# buttons.net
KiCad netlist of a schematic drawn in EAGLE
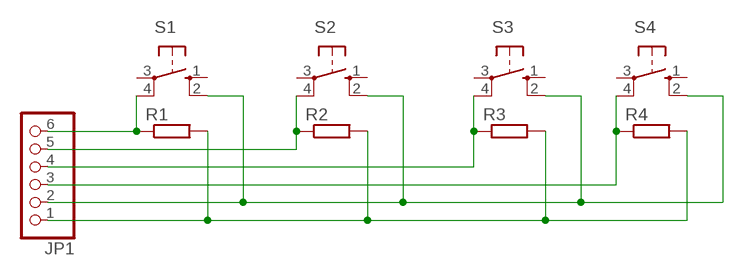
[diagram p0: schematic, sheet 1]

(export (version "E")
  (design (tool "Eeschema 10.0.6"))
  (components
    (comp (ref "JP1")
      (value "PINHD-1X6/90")
      (footprint "eagle-import:1X06_90")
      (libsource (lib "eagle-import") (part "PINHD-1X6/90"))
    )
    (comp (ref "R1")
      (value "R-EU_0207/10")
      (footprint "eagle-import:0207_10")
      (libsource (lib "eagle-import") (part "R-EU_0207/10"))
    )
    (comp (ref "R2")
      (value "R-EU_0207/10")
      (footprint "eagle-import:0207_10")
      (libsource (lib "eagle-import") (part "R-EU_0207/10"))
    )
    (comp (ref "R3")
      (value "R-EU_0207/10")
      (footprint "eagle-import:0207_10")
      (libsource (lib "eagle-import") (part "R-EU_0207/10"))
    )
    (comp (ref "R4")
      (value "R-EU_0207/10")
      (footprint "eagle-import:0207_10")
      (libsource (lib "eagle-import") (part "R-EU_0207/10"))
    )
    (comp (ref "S1")
      (value "10-XX")
      (footprint "eagle-import:B3F-10XX")
      (fields (field (name "MPN") "B3F-1000"))
      (libsource (lib "eagle-import") (part "10-XX"))
    )
    (comp (ref "S2")
      (value "10-XX")
      (footprint "eagle-import:B3F-10XX")
      (fields (field (name "MPN") "B3F-1000"))
      (libsource (lib "eagle-import") (part "10-XX"))
    )
    (comp (ref "S3")
      (value "10-XX")
      (footprint "eagle-import:B3F-10XX")
      (fields (field (name "MPN") "B3F-1000"))
      (libsource (lib "eagle-import") (part "10-XX"))
    )
    (comp (ref "S4")
      (value "10-XX")
      (footprint "eagle-import:B3F-10XX")
      (fields (field (name "MPN") "B3F-1000"))
      (libsource (lib "eagle-import") (part "10-XX"))
    )
  )
  (nets
    (net (code "1") (name "Net-(JP1-Pad1)") (class "Default")
      (node (ref "JP1") (pin "1") (pinfunction "1_1") (pintype "passive"))
      (node (ref "R1") (pin "2") (pinfunction "2_2") (pintype "passive"))
      (node (ref "R2") (pin "2") (pinfunction "2_2") (pintype "passive"))
      (node (ref "R3") (pin "2") (pinfunction "2_2") (pintype "passive"))
      (node (ref "R4") (pin "2") (pinfunction "2_2") (pintype "passive"))
    )
    (net (code "2") (name "Net-(S1-P1)") (class "Default")
      (node (ref "JP1") (pin "6") (pinfunction "6_6") (pintype "passive"))
      (node (ref "R1") (pin "1") (pinfunction "1_1") (pintype "passive"))
      (node (ref "S1") (pin "4") (pinfunction "P1_4") (pintype "passive"))
    )
    (net (code "3") (name "Net-(S1-S1)") (class "Default")
      (node (ref "JP1") (pin "2") (pinfunction "2_2") (pintype "passive"))
      (node (ref "S1") (pin "2") (pinfunction "S1_2") (pintype "passive"))
      (node (ref "S2") (pin "2") (pinfunction "S1_2") (pintype "passive"))
      (node (ref "S3") (pin "2") (pinfunction "S1_2") (pintype "passive"))
      (node (ref "S4") (pin "2") (pinfunction "S1_2") (pintype "passive"))
    )
    (net (code "4") (name "Net-(S2-P1)") (class "Default")
      (node (ref "JP1") (pin "5") (pinfunction "5_5") (pintype "passive"))
      (node (ref "R2") (pin "1") (pinfunction "1_1") (pintype "passive"))
      (node (ref "S2") (pin "4") (pinfunction "P1_4") (pintype "passive"))
    )
    (net (code "5") (name "Net-(S3-P1)") (class "Default")
      (node (ref "JP1") (pin "4") (pinfunction "4_4") (pintype "passive"))
      (node (ref "R3") (pin "1") (pinfunction "1_1") (pintype "passive"))
      (node (ref "S3") (pin "4") (pinfunction "P1_4") (pintype "passive"))
    )
    (net (code "6") (name "Net-(S4-P1)") (class "Default")
      (node (ref "JP1") (pin "3") (pinfunction "3_3") (pintype "passive"))
      (node (ref "R4") (pin "1") (pinfunction "1_1") (pintype "passive"))
      (node (ref "S4") (pin "4") (pinfunction "P1_4") (pintype "passive"))
    )
    (net (code "7") (name "unconnected-(S1-P-Pad3)") (class "Default")
      (node (ref "S1") (pin "3") (pinfunction "P_3") (pintype "passive"))
    )
    (net (code "8") (name "unconnected-(S1-S-Pad1)") (class "Default")
      (node (ref "S1") (pin "1") (pinfunction "S_1") (pintype "passive"))
    )
    (net (code "9") (name "unconnected-(S2-P-Pad3)") (class "Default")
      (node (ref "S2") (pin "3") (pinfunction "P_3") (pintype "passive"))
    )
    (net (code "10") (name "unconnected-(S2-S-Pad1)") (class "Default")
      (node (ref "S2") (pin "1") (pinfunction "S_1") (pintype "passive"))
    )
    (net (code "11") (name "unconnected-(S3-P-Pad3)") (class "Default")
      (node (ref "S3") (pin "3") (pinfunction "P_3") (pintype "passive"))
    )
    (net (code "12") (name "unconnected-(S3-S-Pad1)") (class "Default")
      (node (ref "S3") (pin "1") (pinfunction "S_1") (pintype "passive"))
    )
    (net (code "13") (name "unconnected-(S4-P-Pad3)") (class "Default")
      (node (ref "S4") (pin "3") (pinfunction "P_3") (pintype "passive"))
    )
    (net (code "14") (name "unconnected-(S4-S-Pad1)") (class "Default")
      (node (ref "S4") (pin "1") (pinfunction "S_1") (pintype "passive"))
    )
  )
)
